# h-bridge-mk1.net
KiCad netlist of a schematic drawn in EAGLE
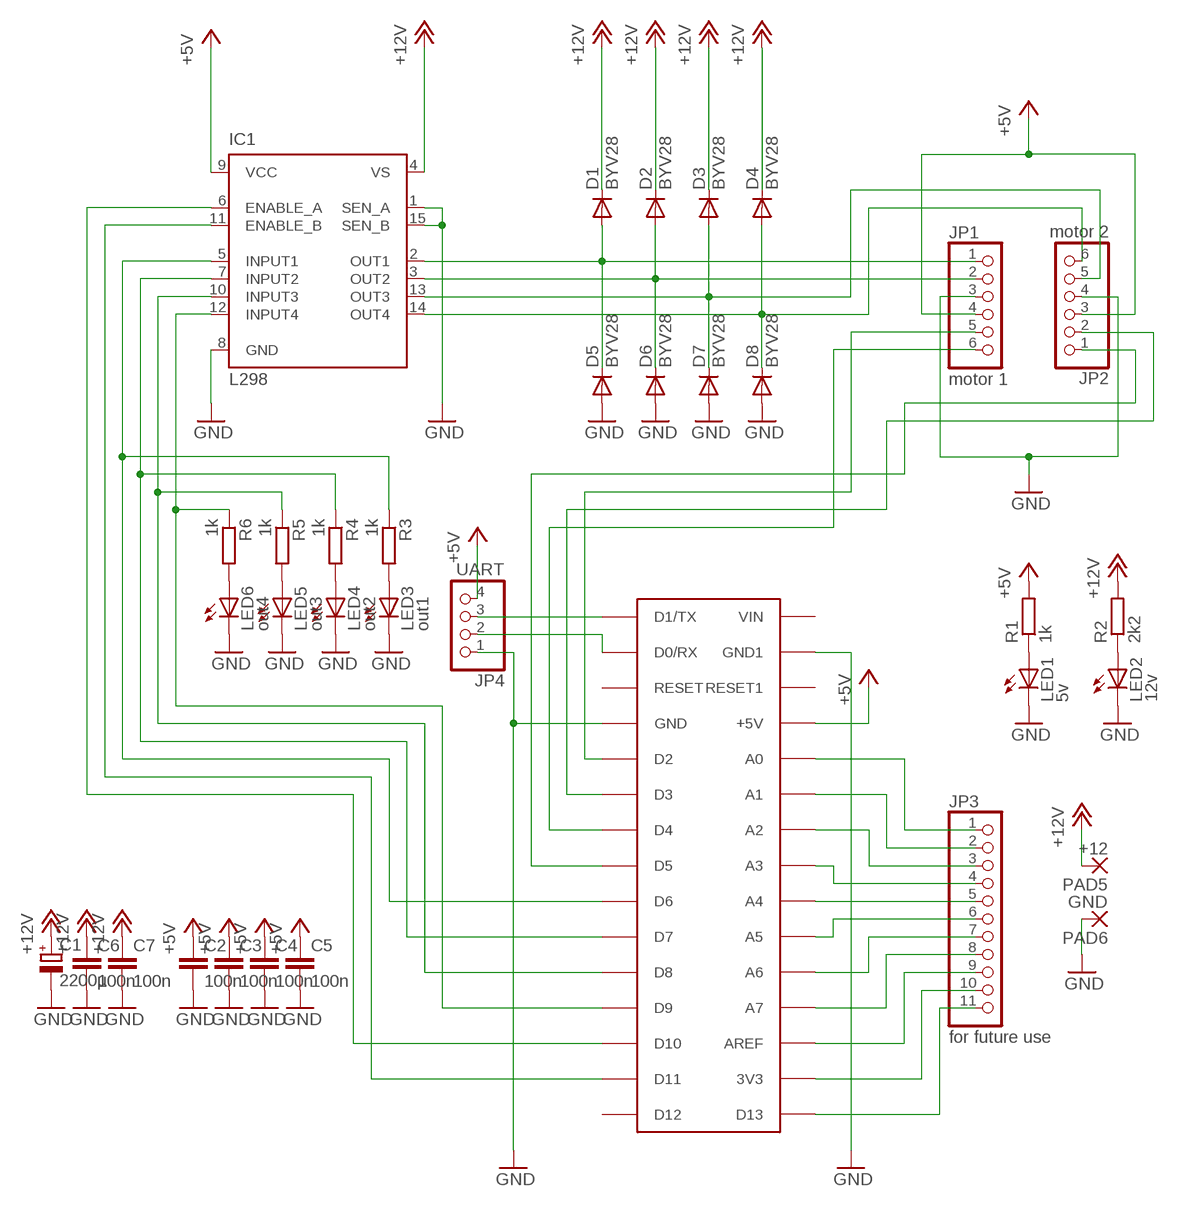
[diagram p0: schematic, sheet 1]

(export (version "E")
  (design (tool "Eeschema 10.0.6"))
  (components
    (comp (ref "C1")
      (value "2200µ")
      (footprint "eagle-import:E5-10,5")
      (libsource (lib "eagle-import") (part "CPOL-EUE5-10.5"))
    )
    (comp (ref "C2")
      (value "100n")
      (footprint "eagle-import:C025-025X050")
      (libsource (lib "eagle-import") (part "C-EU025-025X050"))
    )
    (comp (ref "C3")
      (value "100n")
      (footprint "eagle-import:C025-025X050")
      (libsource (lib "eagle-import") (part "C-EU025-025X050"))
    )
    (comp (ref "C4")
      (value "100n")
      (footprint "eagle-import:C025-025X050")
      (libsource (lib "eagle-import") (part "C-EU025-025X050"))
    )
    (comp (ref "C5")
      (value "100n")
      (footprint "eagle-import:C025-025X050")
      (libsource (lib "eagle-import") (part "C-EU025-025X050"))
    )
    (comp (ref "C6")
      (value "100n")
      (footprint "eagle-import:C025-025X050")
      (libsource (lib "eagle-import") (part "C-EU025-025X050"))
    )
    (comp (ref "C7")
      (value "100n")
      (footprint "eagle-import:C025-025X050")
      (libsource (lib "eagle-import") (part "C-EU025-025X050"))
    )
    (comp (ref "D1")
      (value "BYV28")
      (footprint "eagle-import:SOD64-10")
      (libsource (lib "eagle-import") (part "BYV28"))
    )
    (comp (ref "D2")
      (value "BYV28")
      (footprint "eagle-import:SOD64-10")
      (libsource (lib "eagle-import") (part "BYV28"))
    )
    (comp (ref "D3")
      (value "BYV28")
      (footprint "eagle-import:SOD64-10")
      (libsource (lib "eagle-import") (part "BYV28"))
    )
    (comp (ref "D4")
      (value "BYV28")
      (footprint "eagle-import:SOD64-10")
      (libsource (lib "eagle-import") (part "BYV28"))
    )
    (comp (ref "D5")
      (value "BYV28")
      (footprint "eagle-import:SOD64-10")
      (libsource (lib "eagle-import") (part "BYV28"))
    )
    (comp (ref "D6")
      (value "BYV28")
      (footprint "eagle-import:SOD64-10")
      (libsource (lib "eagle-import") (part "BYV28"))
    )
    (comp (ref "D7")
      (value "BYV28")
      (footprint "eagle-import:SOD64-10")
      (libsource (lib "eagle-import") (part "BYV28"))
    )
    (comp (ref "D8")
      (value "BYV28")
      (footprint "eagle-import:SOD64-10")
      (libsource (lib "eagle-import") (part "BYV28"))
    )
    (comp (ref "IC1")
      (value "L298")
      (footprint "eagle-import:MULTIWATT-15")
      (fields (field (name "MPN") "L298N"))
      (libsource (lib "eagle-import") (part "L298"))
    )
    (comp (ref "JP1")
      (value "motor 1")
      (footprint "eagle-import:1X06")
      (libsource (lib "eagle-import") (part "PINHD-1X6"))
    )
    (comp (ref "JP2")
      (value "motor 2")
      (footprint "eagle-import:1X06")
      (libsource (lib "eagle-import") (part "PINHD-1X6"))
    )
    (comp (ref "JP3")
      (value "for future use")
      (footprint "eagle-import:1X11")
      (libsource (lib "eagle-import") (part "PINHD-1X11"))
    )
    (comp (ref "JP4")
      (value "UART")
      (footprint "eagle-import:1X04")
      (libsource (lib "eagle-import") (part "PINHD-1X4"))
    )
    (comp (ref "LED1")
      (value "5v")
      (footprint "eagle-import:LED3MM")
      (libsource (lib "eagle-import") (part "LED3MM"))
    )
    (comp (ref "LED2")
      (value "12v")
      (footprint "eagle-import:LED3MM")
      (libsource (lib "eagle-import") (part "LED3MM"))
    )
    (comp (ref "LED3")
      (value "out1")
      (footprint "eagle-import:LED3MM")
      (libsource (lib "eagle-import") (part "LED3MM"))
    )
    (comp (ref "LED4")
      (value "out2")
      (footprint "eagle-import:LED3MM")
      (libsource (lib "eagle-import") (part "LED3MM"))
    )
    (comp (ref "LED5")
      (value "out3")
      (footprint "eagle-import:LED3MM")
      (libsource (lib "eagle-import") (part "LED3MM"))
    )
    (comp (ref "LED6")
      (value "out4")
      (footprint "eagle-import:LED3MM")
      (libsource (lib "eagle-import") (part "LED3MM"))
    )
    (comp (ref "PAD5")
      (value "+12")
      (footprint "eagle-import:3,81_1,1")
      (libsource (lib "eagle-import") (part "3,81/1,1"))
    )
    (comp (ref "PAD6")
      (value "GND")
      (footprint "eagle-import:3,81_1,1")
      (libsource (lib "eagle-import") (part "3,81/1,1"))
    )
    (comp (ref "R1")
      (value "1k")
      (footprint "eagle-import:0207_10")
      (libsource (lib "eagle-import") (part "R-EU_0207/10"))
    )
    (comp (ref "R2")
      (value "2k2")
      (footprint "eagle-import:0207_10")
      (libsource (lib "eagle-import") (part "R-EU_0207/10"))
    )
    (comp (ref "R3")
      (value "1k")
      (footprint "eagle-import:0207_10")
      (libsource (lib "eagle-import") (part "R-EU_0207/10"))
    )
    (comp (ref "R4")
      (value "1k")
      (footprint "eagle-import:0207_10")
      (libsource (lib "eagle-import") (part "R-EU_0207/10"))
    )
    (comp (ref "R5")
      (value "1k")
      (footprint "eagle-import:0207_10")
      (libsource (lib "eagle-import") (part "R-EU_0207/10"))
    )
    (comp (ref "R6")
      (value "1k")
      (footprint "eagle-import:0207_10")
      (libsource (lib "eagle-import") (part "R-EU_0207/10"))
    )
    (comp (ref "U$1")
      (value "ARDUINONANO")
      (footprint "eagle-import:PDIP-32")
      (libsource (lib "eagle-import") (part "ARDUINONANO"))
    )
  )
  (nets
    (net (code "1") (name "+5V") (class "Default")
      (node (ref "C2") (pin "1") (pinfunction "1_1") (pintype "passive"))
      (node (ref "C3") (pin "1") (pinfunction "1_1") (pintype "passive"))
      (node (ref "C4") (pin "1") (pinfunction "1_1") (pintype "passive"))
      (node (ref "C5") (pin "1") (pinfunction "1_1") (pintype "passive"))
      (node (ref "IC1") (pin "9") (pinfunction "VCC_9") (pintype "power_in"))
      (node (ref "JP1") (pin "4") (pinfunction "4_4") (pintype "passive"))
      (node (ref "JP2") (pin "3") (pinfunction "3_3") (pintype "passive"))
      (node (ref "JP4") (pin "4") (pinfunction "4_4") (pintype "passive"))
      (node (ref "R1") (pin "2") (pinfunction "2_2") (pintype "passive"))
      (node (ref "U$1") (pin "+5V") (pinfunction "+5V_+5V") (pintype "bidirectional"))
    )
    (net (code "2") (name "+12V") (class "Default")
      (node (ref "C1") (pin "+") (pinfunction "+_+") (pintype "passive"))
      (node (ref "C6") (pin "1") (pinfunction "1_1") (pintype "passive"))
      (node (ref "C7") (pin "1") (pinfunction "1_1") (pintype "passive"))
      (node (ref "D1") (pin "C") (pinfunction "C_C") (pintype "passive"))
      (node (ref "D2") (pin "C") (pinfunction "C_C") (pintype "passive"))
      (node (ref "D3") (pin "C") (pinfunction "C_C") (pintype "passive"))
      (node (ref "D4") (pin "C") (pinfunction "C_C") (pintype "passive"))
      (node (ref "IC1") (pin "4") (pinfunction "VS_4") (pintype "power_in"))
      (node (ref "PAD5") (pin "1") (pinfunction "P_1") (pintype "passive"))
      (node (ref "R2") (pin "2") (pinfunction "2_2") (pintype "passive"))
    )
    (net (code "3") (name "GND") (class "Default")
      (node (ref "C1") (pin "-") (pinfunction "-_-") (pintype "passive"))
      (node (ref "C2") (pin "2") (pinfunction "2_2") (pintype "passive"))
      (node (ref "C3") (pin "2") (pinfunction "2_2") (pintype "passive"))
      (node (ref "C4") (pin "2") (pinfunction "2_2") (pintype "passive"))
      (node (ref "C5") (pin "2") (pinfunction "2_2") (pintype "passive"))
      (node (ref "C6") (pin "2") (pinfunction "2_2") (pintype "passive"))
      (node (ref "C7") (pin "2") (pinfunction "2_2") (pintype "passive"))
      (node (ref "D5") (pin "A") (pinfunction "A_A") (pintype "passive"))
      (node (ref "D6") (pin "A") (pinfunction "A_A") (pintype "passive"))
      (node (ref "D7") (pin "A") (pinfunction "A_A") (pintype "passive"))
      (node (ref "D8") (pin "A") (pinfunction "A_A") (pintype "passive"))
      (node (ref "IC1") (pin "1") (pinfunction "SEN_A_1") (pintype "input"))
      (node (ref "IC1") (pin "15") (pinfunction "SEN_B_15") (pintype "input"))
      (node (ref "IC1") (pin "8") (pinfunction "GND_8") (pintype "power_in"))
      (node (ref "JP1") (pin "3") (pinfunction "3_3") (pintype "passive"))
      (node (ref "JP2") (pin "4") (pinfunction "4_4") (pintype "passive"))
      (node (ref "JP4") (pin "1") (pinfunction "1_1") (pintype "passive"))
      (node (ref "LED1") (pin "K") (pinfunction "C_K") (pintype "passive"))
      (node (ref "LED2") (pin "K") (pinfunction "C_K") (pintype "passive"))
      (node (ref "LED3") (pin "K") (pinfunction "C_K") (pintype "passive"))
      (node (ref "LED4") (pin "K") (pinfunction "C_K") (pintype "passive"))
      (node (ref "LED5") (pin "K") (pinfunction "C_K") (pintype "passive"))
      (node (ref "LED6") (pin "K") (pinfunction "C_K") (pintype "passive"))
      (node (ref "PAD6") (pin "1") (pinfunction "P_1") (pintype "passive"))
      (node (ref "U$1") (pin "GND") (pinfunction "GND_GND") (pintype "bidirectional"))
      (node (ref "U$1") (pin "GND1") (pinfunction "GND1_GND1") (pintype "bidirectional"))
    )
    (net (code "4") (name "Net-(IC1-ENABLE_A)") (class "Default")
      (node (ref "IC1") (pin "6") (pinfunction "ENABLE_A_6") (pintype "input"))
      (node (ref "U$1") (pin "D10") (pinfunction "D10_D10") (pintype "bidirectional"))
    )
    (net (code "5") (name "Net-(IC1-ENABLE_B)") (class "Default")
      (node (ref "IC1") (pin "11") (pinfunction "ENABLE_B_11") (pintype "input"))
      (node (ref "U$1") (pin "D11") (pinfunction "D11_D11") (pintype "bidirectional"))
    )
    (net (code "6") (name "Net-(IC1-INPUT1)") (class "Default")
      (node (ref "IC1") (pin "5") (pinfunction "INPUT1_5") (pintype "input"))
      (node (ref "R3") (pin "1") (pinfunction "1_1") (pintype "passive"))
      (node (ref "U$1") (pin "D6") (pinfunction "D6_D6") (pintype "bidirectional"))
    )
    (net (code "7") (name "Net-(IC1-INPUT2)") (class "Default")
      (node (ref "IC1") (pin "7") (pinfunction "INPUT2_7") (pintype "input"))
      (node (ref "R4") (pin "1") (pinfunction "1_1") (pintype "passive"))
      (node (ref "U$1") (pin "D7") (pinfunction "D7_D7") (pintype "bidirectional"))
    )
    (net (code "8") (name "Net-(IC1-INPUT3)") (class "Default")
      (node (ref "IC1") (pin "10") (pinfunction "INPUT3_10") (pintype "input"))
      (node (ref "R5") (pin "1") (pinfunction "1_1") (pintype "passive"))
      (node (ref "U$1") (pin "D8") (pinfunction "D8_D8") (pintype "bidirectional"))
    )
    (net (code "9") (name "Net-(IC1-INPUT4)") (class "Default")
      (node (ref "IC1") (pin "12") (pinfunction "INPUT4_12") (pintype "input"))
      (node (ref "R6") (pin "1") (pinfunction "1_1") (pintype "passive"))
      (node (ref "U$1") (pin "D9") (pinfunction "D9_D9") (pintype "bidirectional"))
    )
    (net (code "10") (name "Net-(IC1-OUT1)") (class "Default")
      (node (ref "D1") (pin "A") (pinfunction "A_A") (pintype "passive"))
      (node (ref "D5") (pin "C") (pinfunction "C_C") (pintype "passive"))
      (node (ref "IC1") (pin "2") (pinfunction "OUT1_2") (pintype "output"))
      (node (ref "JP1") (pin "1") (pinfunction "1_1") (pintype "passive"))
    )
    (net (code "11") (name "Net-(IC1-OUT2)") (class "Default")
      (node (ref "D2") (pin "A") (pinfunction "A_A") (pintype "passive"))
      (node (ref "D6") (pin "C") (pinfunction "C_C") (pintype "passive"))
      (node (ref "IC1") (pin "3") (pinfunction "OUT2_3") (pintype "output"))
      (node (ref "JP1") (pin "2") (pinfunction "2_2") (pintype "passive"))
    )
    (net (code "12") (name "Net-(IC1-OUT3)") (class "Default")
      (node (ref "D3") (pin "A") (pinfunction "A_A") (pintype "passive"))
      (node (ref "D7") (pin "C") (pinfunction "C_C") (pintype "passive"))
      (node (ref "IC1") (pin "13") (pinfunction "OUT3_13") (pintype "output"))
      (node (ref "JP2") (pin "5") (pinfunction "5_5") (pintype "passive"))
    )
    (net (code "13") (name "Net-(IC1-OUT4)") (class "Default")
      (node (ref "D4") (pin "A") (pinfunction "A_A") (pintype "passive"))
      (node (ref "D8") (pin "C") (pinfunction "C_C") (pintype "passive"))
      (node (ref "IC1") (pin "14") (pinfunction "OUT4_14") (pintype "output"))
      (node (ref "JP2") (pin "6") (pinfunction "6_6") (pintype "passive"))
    )
    (net (code "14") (name "Net-(JP1-Pad5)") (class "Default")
      (node (ref "JP1") (pin "5") (pinfunction "5_5") (pintype "passive"))
      (node (ref "U$1") (pin "D2") (pinfunction "D2_D2") (pintype "bidirectional"))
    )
    (net (code "15") (name "Net-(JP1-Pad6)") (class "Default")
      (node (ref "JP1") (pin "6") (pinfunction "6_6") (pintype "passive"))
      (node (ref "U$1") (pin "D4") (pinfunction "D4_D4") (pintype "bidirectional"))
    )
    (net (code "16") (name "Net-(JP2-Pad1)") (class "Default")
      (node (ref "JP2") (pin "1") (pinfunction "1_1") (pintype "passive"))
      (node (ref "U$1") (pin "D5") (pinfunction "D5_D5") (pintype "bidirectional"))
    )
    (net (code "17") (name "Net-(JP2-Pad2)") (class "Default")
      (node (ref "JP2") (pin "2") (pinfunction "2_2") (pintype "passive"))
      (node (ref "U$1") (pin "D3") (pinfunction "D3_D3") (pintype "bidirectional"))
    )
    (net (code "18") (name "Net-(JP3-Pad1)") (class "Default")
      (node (ref "JP3") (pin "1") (pinfunction "1_1") (pintype "passive"))
      (node (ref "U$1") (pin "A0") (pinfunction "A0_A0") (pintype "bidirectional"))
    )
    (net (code "19") (name "Net-(JP3-Pad2)") (class "Default")
      (node (ref "JP3") (pin "2") (pinfunction "2_2") (pintype "passive"))
      (node (ref "U$1") (pin "A1") (pinfunction "A1_A1") (pintype "bidirectional"))
    )
    (net (code "20") (name "Net-(JP3-Pad3)") (class "Default")
      (node (ref "JP3") (pin "3") (pinfunction "3_3") (pintype "passive"))
      (node (ref "U$1") (pin "A2") (pinfunction "A2_A2") (pintype "bidirectional"))
    )
    (net (code "21") (name "Net-(JP3-Pad4)") (class "Default")
      (node (ref "JP3") (pin "4") (pinfunction "4_4") (pintype "passive"))
      (node (ref "U$1") (pin "A3") (pinfunction "A3_A3") (pintype "bidirectional"))
    )
    (net (code "22") (name "Net-(JP3-Pad5)") (class "Default")
      (node (ref "JP3") (pin "5") (pinfunction "5_5") (pintype "passive"))
      (node (ref "U$1") (pin "A4") (pinfunction "A4_A4") (pintype "bidirectional"))
    )
    (net (code "23") (name "Net-(JP3-Pad6)") (class "Default")
      (node (ref "JP3") (pin "6") (pinfunction "6_6") (pintype "passive"))
      (node (ref "U$1") (pin "A5") (pinfunction "A5_A5") (pintype "bidirectional"))
    )
    (net (code "24") (name "Net-(JP3-Pad7)") (class "Default")
      (node (ref "JP3") (pin "7") (pinfunction "7_7") (pintype "passive"))
      (node (ref "U$1") (pin "A6") (pinfunction "A6_A6") (pintype "bidirectional"))
    )
    (net (code "25") (name "Net-(JP3-Pad8)") (class "Default")
      (node (ref "JP3") (pin "8") (pinfunction "8_8") (pintype "passive"))
      (node (ref "U$1") (pin "A7") (pinfunction "A7_A7") (pintype "bidirectional"))
    )
    (net (code "26") (name "Net-(JP3-Pad9)") (class "Default")
      (node (ref "JP3") (pin "9") (pinfunction "9_9") (pintype "passive"))
      (node (ref "U$1") (pin "AREF") (pinfunction "AREF_AREF") (pintype "bidirectional"))
    )
    (net (code "27") (name "Net-(JP3-Pad10)") (class "Default")
      (node (ref "JP3") (pin "10") (pinfunction "10_10") (pintype "passive"))
      (node (ref "U$1") (pin "3V3") (pinfunction "3V3_3V3") (pintype "bidirectional"))
    )
    (net (code "28") (name "Net-(JP3-Pad11)") (class "Default")
      (node (ref "JP3") (pin "11") (pinfunction "11_11") (pintype "passive"))
      (node (ref "U$1") (pin "D13") (pinfunction "D13_D13") (pintype "bidirectional"))
    )
    (net (code "29") (name "Net-(JP4-Pad2)") (class "Default")
      (node (ref "JP4") (pin "2") (pinfunction "2_2") (pintype "passive"))
      (node (ref "U$1") (pin "D0/RX") (pinfunction "D0/RX_D0/RX") (pintype "bidirectional"))
    )
    (net (code "30") (name "Net-(JP4-Pad3)") (class "Default")
      (node (ref "JP4") (pin "3") (pinfunction "3_3") (pintype "passive"))
      (node (ref "U$1") (pin "D1/TX") (pinfunction "D1/TX_D1/TX") (pintype "bidirectional"))
    )
    (net (code "31") (name "Net-(LED1-PadA)") (class "Default")
      (node (ref "LED1") (pin "A") (pinfunction "A_A") (pintype "passive"))
      (node (ref "R1") (pin "1") (pinfunction "1_1") (pintype "passive"))
    )
    (net (code "32") (name "Net-(LED2-PadA)") (class "Default")
      (node (ref "LED2") (pin "A") (pinfunction "A_A") (pintype "passive"))
      (node (ref "R2") (pin "1") (pinfunction "1_1") (pintype "passive"))
    )
    (net (code "33") (name "Net-(LED3-PadA)") (class "Default")
      (node (ref "LED3") (pin "A") (pinfunction "A_A") (pintype "passive"))
      (node (ref "R3") (pin "2") (pinfunction "2_2") (pintype "passive"))
    )
    (net (code "34") (name "Net-(LED4-PadA)") (class "Default")
      (node (ref "LED4") (pin "A") (pinfunction "A_A") (pintype "passive"))
      (node (ref "R4") (pin "2") (pinfunction "2_2") (pintype "passive"))
    )
    (net (code "35") (name "Net-(LED5-PadA)") (class "Default")
      (node (ref "LED5") (pin "A") (pinfunction "A_A") (pintype "passive"))
      (node (ref "R5") (pin "2") (pinfunction "2_2") (pintype "passive"))
    )
    (net (code "36") (name "Net-(LED6-PadA)") (class "Default")
      (node (ref "LED6") (pin "A") (pinfunction "A_A") (pintype "passive"))
      (node (ref "R6") (pin "2") (pinfunction "2_2") (pintype "passive"))
    )
    (net (code "37") (name "unconnected-(U$1-PadD12)") (class "Default")
      (node (ref "U$1") (pin "D12") (pinfunction "D12_D12") (pintype "bidirectional"))
    )
    (net (code "38") (name "unconnected-(U$1-PadRESET)") (class "Default")
      (node (ref "U$1") (pin "RESET") (pinfunction "RESET_RESET") (pintype "bidirectional"))
    )
    (net (code "39") (name "unconnected-(U$1-PadRESET1)") (class "Default")
      (node (ref "U$1") (pin "RESET1") (pinfunction "RESET1_RESET1") (pintype "bidirectional"))
    )
    (net (code "40") (name "unconnected-(U$1-PadVIN)") (class "Default")
      (node (ref "U$1") (pin "VIN") (pinfunction "VIN_VIN") (pintype "bidirectional"))
    )
  )
)
